# PDC_high_Current_Outputs.net
KiCad netlist of a schematic drawn in Altium Designer
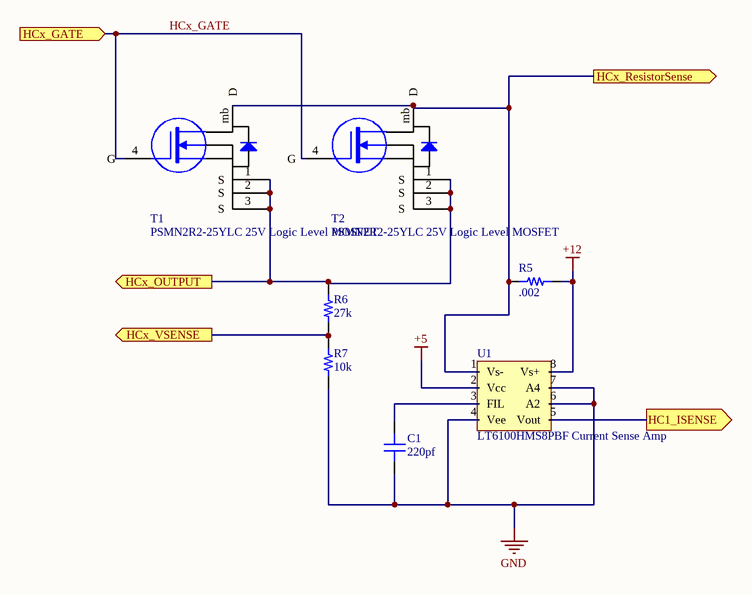
[diagram p0: PDC_high_Current_Outputs.SchDoc]

(export (version "E")
  (design (tool "Eeschema 10.0.6"))
  (components
    (comp (ref "C1")
      (value "220pf")
      (footprint "CAP 0402/1005")
      (fields
        (field (name "Comment") "Capacitor MLCC 220pf 16V CAP 0402/1005")
        (field (name "CREATED_BY") "Nick Mah")
      )
      (libsource (lib "Altium-Lib") (part "Capacitor"))
    )
    (comp (ref "R5")
      (value ".002")
      (footprint "RES 2010/5025")
      (description "Current Sense Resistor")
      (fields
        (field (name "TOLERANCE") "1%")
        (field (name "POWER") "1.5W")
        (field (name "CREATED_BY") "Angel")
      )
      (libsource (lib "") (part "Resistor_1"))
    )
    (comp (ref "R6")
      (value "27k")
      (footprint "RES 0805/2012")
      (fields
        (field (name "TOLERANCE") "10%")
        (field (name "POWER") "1/10W")
        (field (name "Comment") "Resistor 27k 0805 1/10W 10%")
        (field (name "CREATED_BY") "Nick Mah")
      )
      (libsource (lib "Altium-Lib") (part "Resistor"))
    )
    (comp (ref "R7")
      (value "10k")
      (footprint "RES 0402/1005")
      (fields
        (field (name "TOLERANCE") "1%")
        (field (name "POWER") "1/10W")
        (field (name "Comment") "Resistor 10k 0402 1/10W 1%")
        (field (name "CREATED_BY") "Nick Mah")
      )
      (libsource (lib "Altium-Lib") (part "Resistor"))
    )
    (comp (ref "T1")
      (value "PSMN2R2-25YLC 25V Logic Level MOSFET")
      (footprint "LFPAK-SO8")
      (description "N-Channel 25V 100A (Tc) 106W (Tc) Surface Mount LFPAK56, Power-SO8")
      (fields (field (name "MFRPARTNO") "PSMN2R2-25YLC,115") (field (name "CREATED_BY") "Nick"))
      (libsource (lib "Altium-Lib") (part "PSMN2R2-25YLC 25V Logic Level MOSFET"))
    )
    (comp (ref "T2")
      (value "PSMN2R2-25YLC 25V Logic Level MOSFET")
      (footprint "LFPAK-SO8")
      (description "N-Channel 25V 100A (Tc) 106W (Tc) Surface Mount LFPAK56, Power-SO8")
      (fields (field (name "MFRPARTNO") "PSMN2R2-25YLC,115") (field (name "CREATED_BY") "Nick"))
      (libsource (lib "Altium-Lib") (part "PSMN2R2-25YLC 25V Logic Level MOSFET"))
    )
    (comp (ref "U1")
      (value "LT6100HMS8PBF Current Sense Amp")
      (footprint "MSOP-8")
      (fields (field (name "CREATED_BY") "Eddy"))
      (libsource (lib "Altium-Lib") (part "LT6100HMS8PBF Current Sense Amp"))
    )
  )
  (nets
    (net (code "1") (name "+5") (class "Default")
      (node (ref "U1") (pin "2") (pinfunction "Vcc_2") (pintype "input"))
    )
    (net (code "2") (name "+12") (class "Default")
      (node (ref "R5") (pin "2") (pinfunction "2_2") (pintype "passive"))
      (node (ref "U1") (pin "8") (pinfunction "Vs+_8") (pintype "input"))
    )
    (net (code "3") (name "/HC1_ISENSE") (class "Default")
      (node (ref "U1") (pin "5") (pinfunction "Vout_5") (pintype "input"))
    )
    (net (code "4") (name "/HCx_GATE") (class "Default")
      (node (ref "T1") (pin "4") (pinfunction "G_4") (pintype "passive"))
      (node (ref "T2") (pin "4") (pinfunction "G_4") (pintype "passive"))
    )
    (net (code "5") (name "/HCx_OUTPUT") (class "Default")
      (node (ref "R6") (pin "2") (pinfunction "2_2") (pintype "passive"))
      (node (ref "T1") (pin "1") (pinfunction "S_1") (pintype "passive"))
      (node (ref "T1") (pin "2") (pinfunction "S_2") (pintype "passive"))
      (node (ref "T1") (pin "3") (pinfunction "S_3") (pintype "passive"))
      (node (ref "T2") (pin "1") (pinfunction "S_1") (pintype "passive"))
      (node (ref "T2") (pin "2") (pinfunction "S_2") (pintype "passive"))
      (node (ref "T2") (pin "3") (pinfunction "S_3") (pintype "passive"))
    )
    (net (code "6") (name "/HCx_ResistorSense") (class "Default")
      (node (ref "R5") (pin "1") (pinfunction "1_1") (pintype "passive"))
      (node (ref "T1") (pin "mb") (pinfunction "D_mb") (pintype "passive"))
      (node (ref "T2") (pin "mb") (pinfunction "D_mb") (pintype "passive"))
      (node (ref "U1") (pin "1") (pinfunction "Vs-_1") (pintype "input"))
    )
    (net (code "7") (name "/HCx_VSENSE") (class "Default")
      (node (ref "R6") (pin "1") (pinfunction "1_1") (pintype "passive"))
      (node (ref "R7") (pin "2") (pinfunction "2_2") (pintype "passive"))
    )
    (net (code "8") (name "GND") (class "Default")
      (node (ref "C1") (pin "1") (pinfunction "1_1") (pintype "passive"))
      (node (ref "R7") (pin "1") (pinfunction "1_1") (pintype "passive"))
      (node (ref "U1") (pin "4") (pinfunction "Vee_4") (pintype "input"))
      (node (ref "U1") (pin "6") (pinfunction "A2_6") (pintype "input"))
      (node (ref "U1") (pin "7") (pinfunction "A4_7") (pintype "input"))
    )
    (net (code "9") (name "Net-(U1-FIL)") (class "Default")
      (node (ref "C1") (pin "2") (pinfunction "2_2") (pintype "passive"))
      (node (ref "U1") (pin "3") (pinfunction "FIL_3") (pintype "input"))
    )
  )
)
